# MicronetToNMEA.net
KiCad netlist of a schematic drawn in EasyEDA Pro
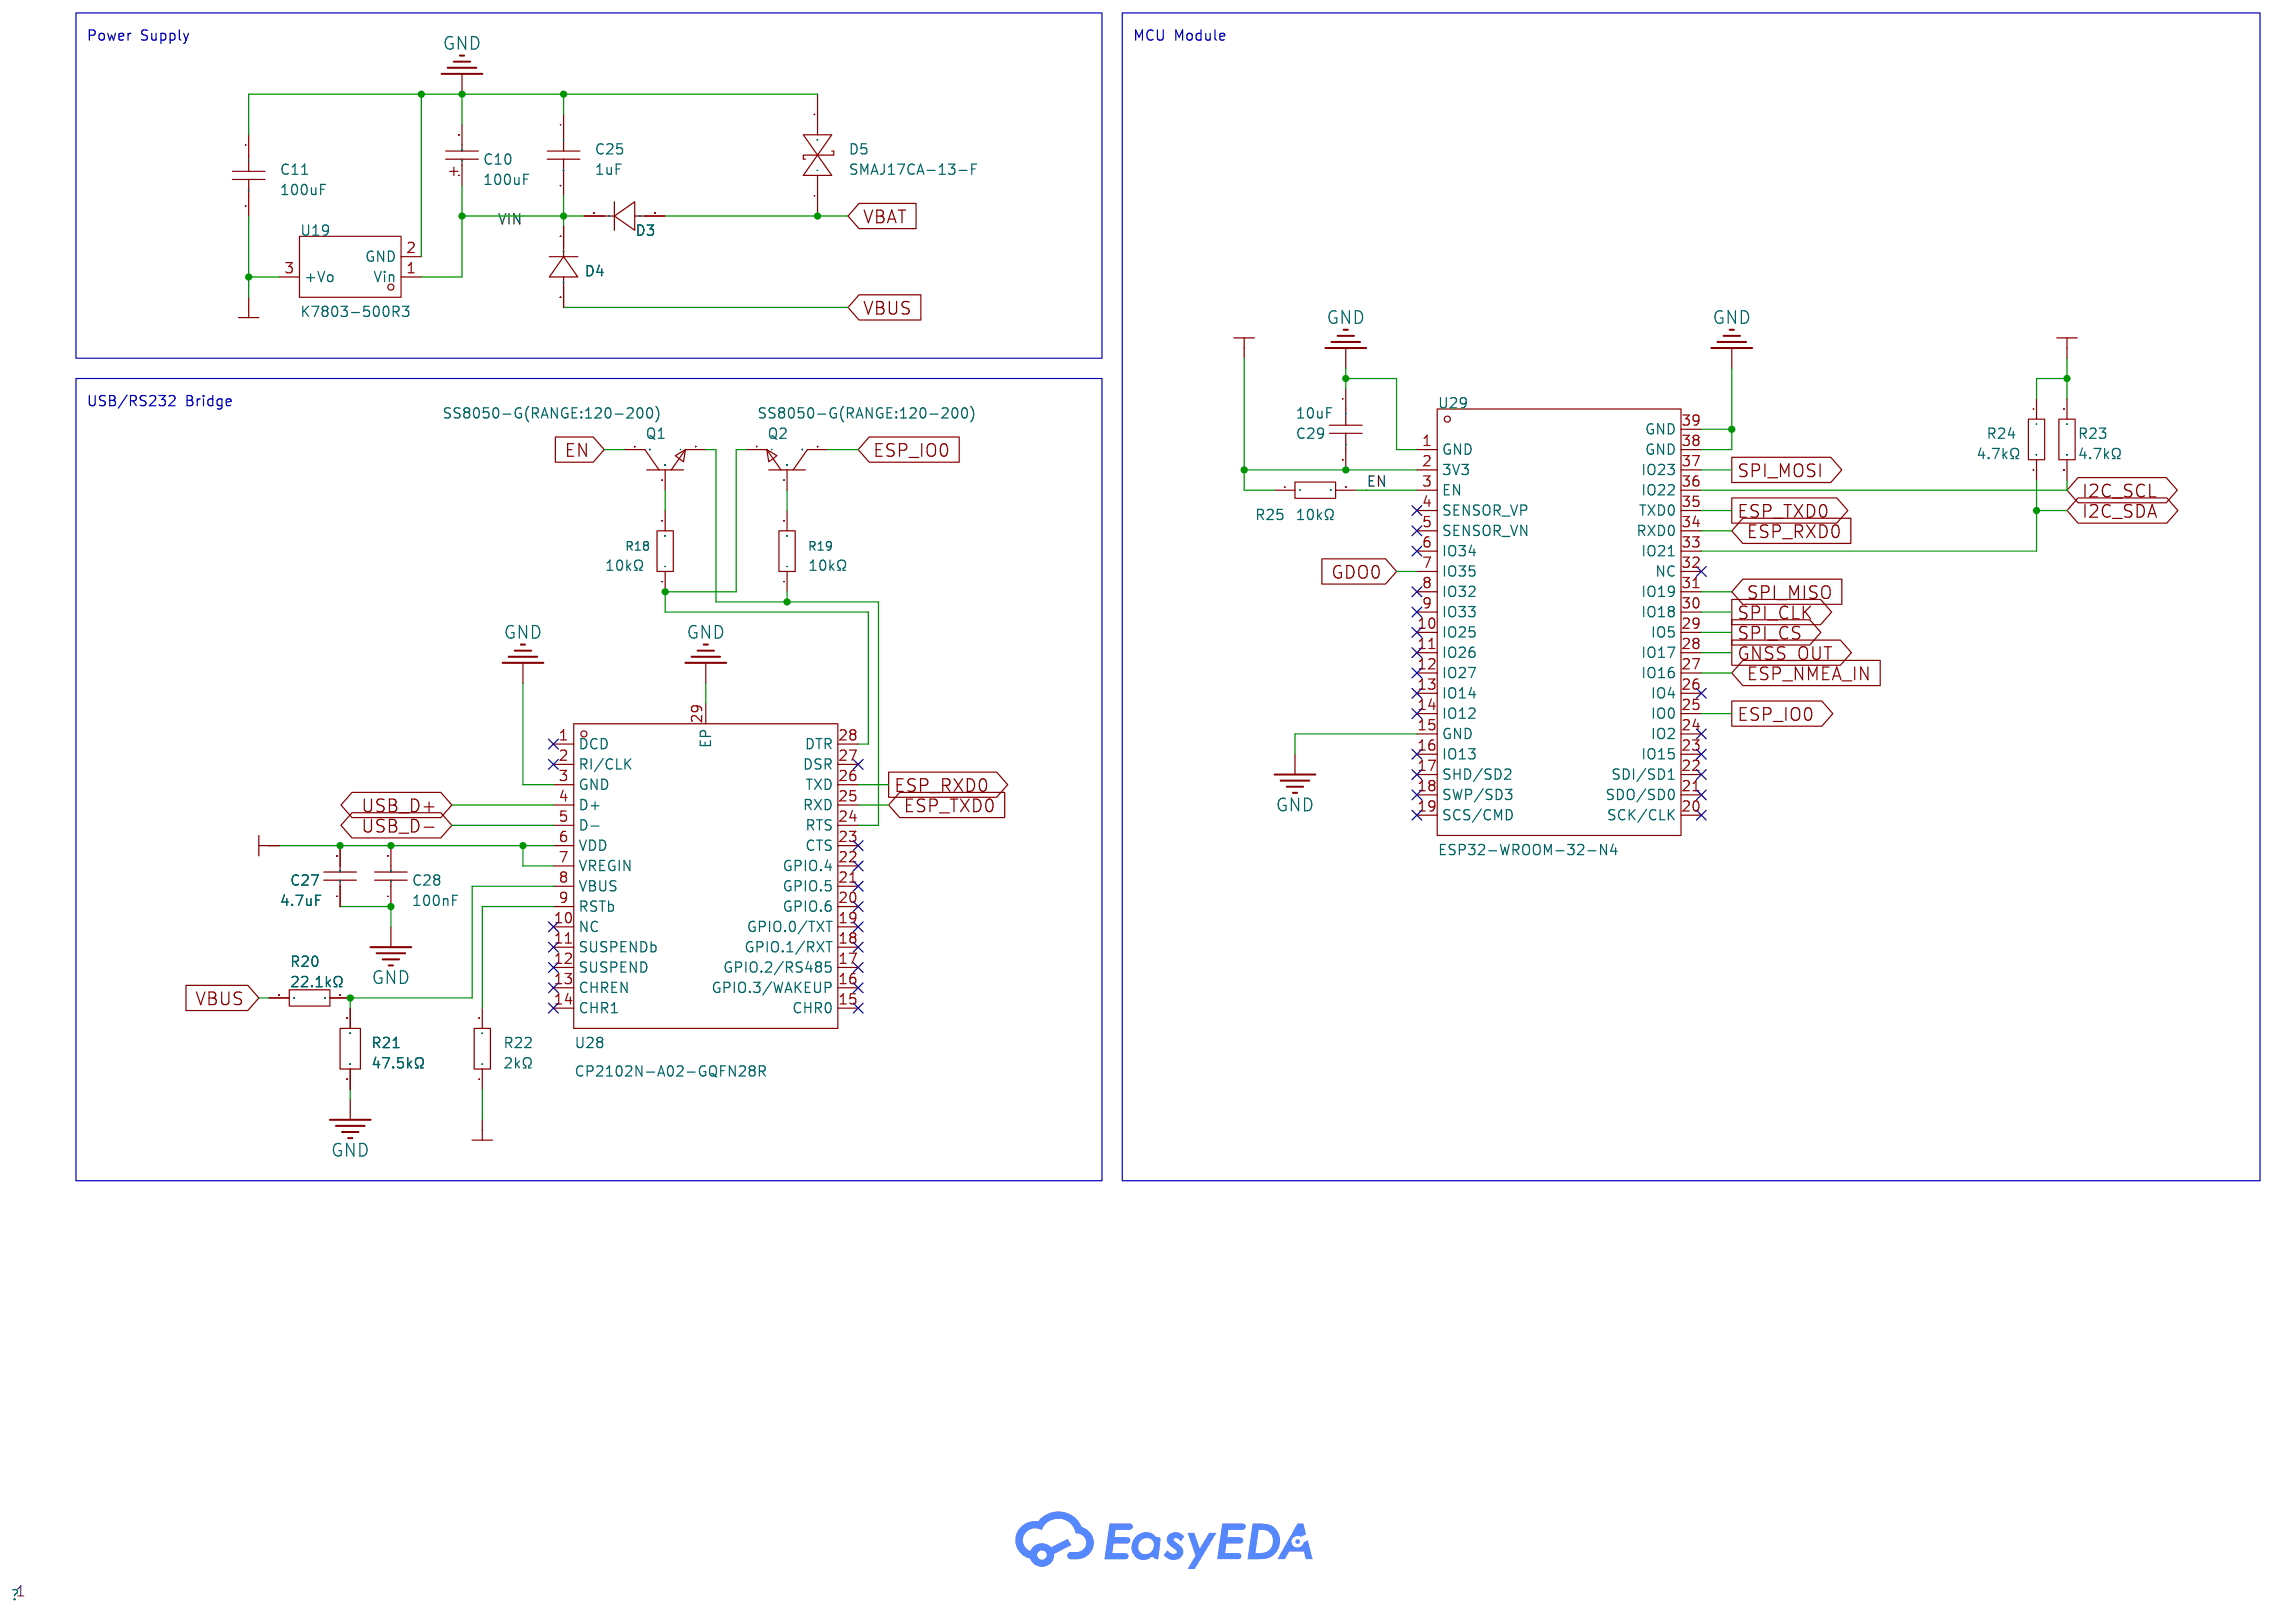
[diagram p0: MCU]
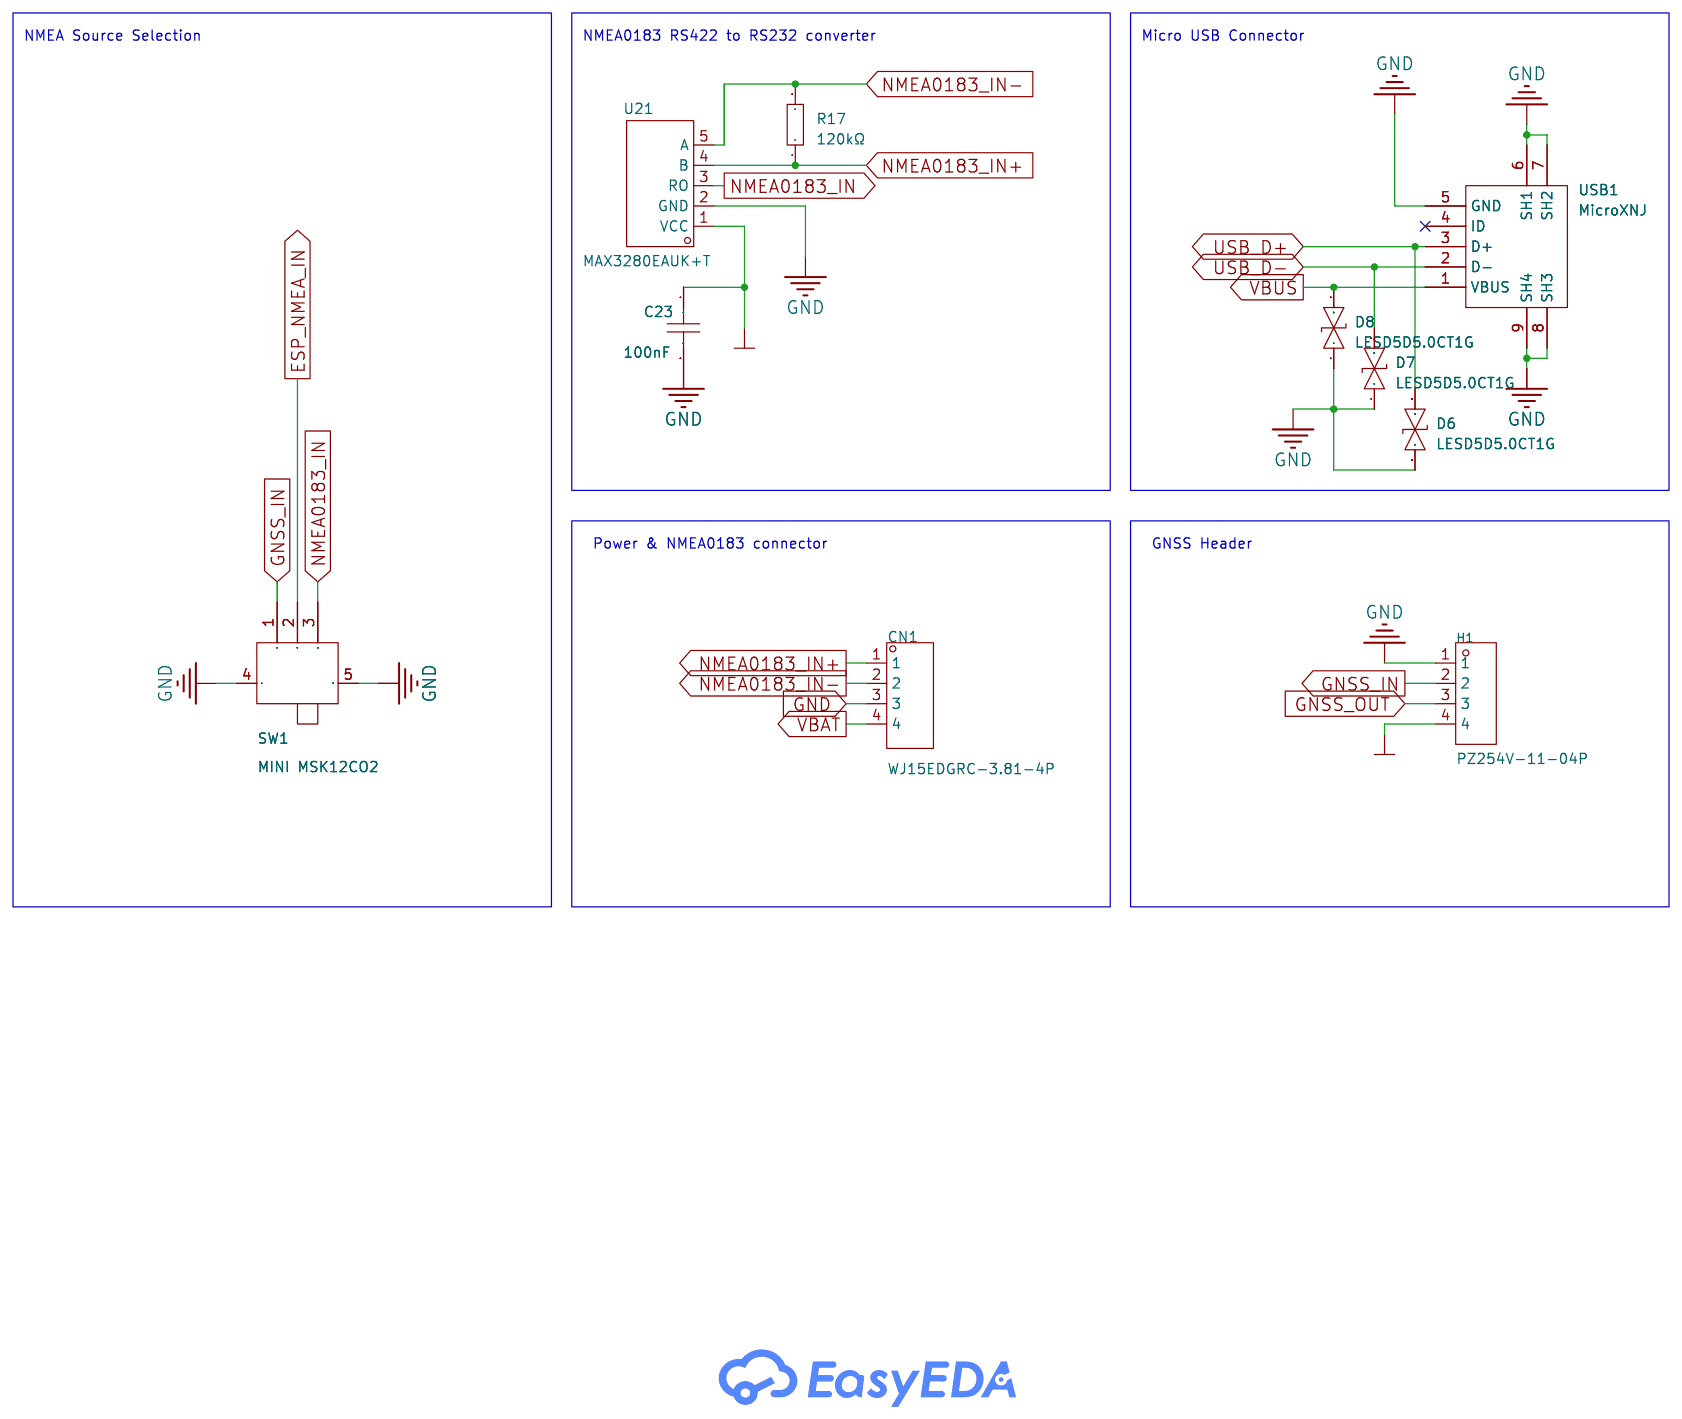
[diagram p1: Peripherals]
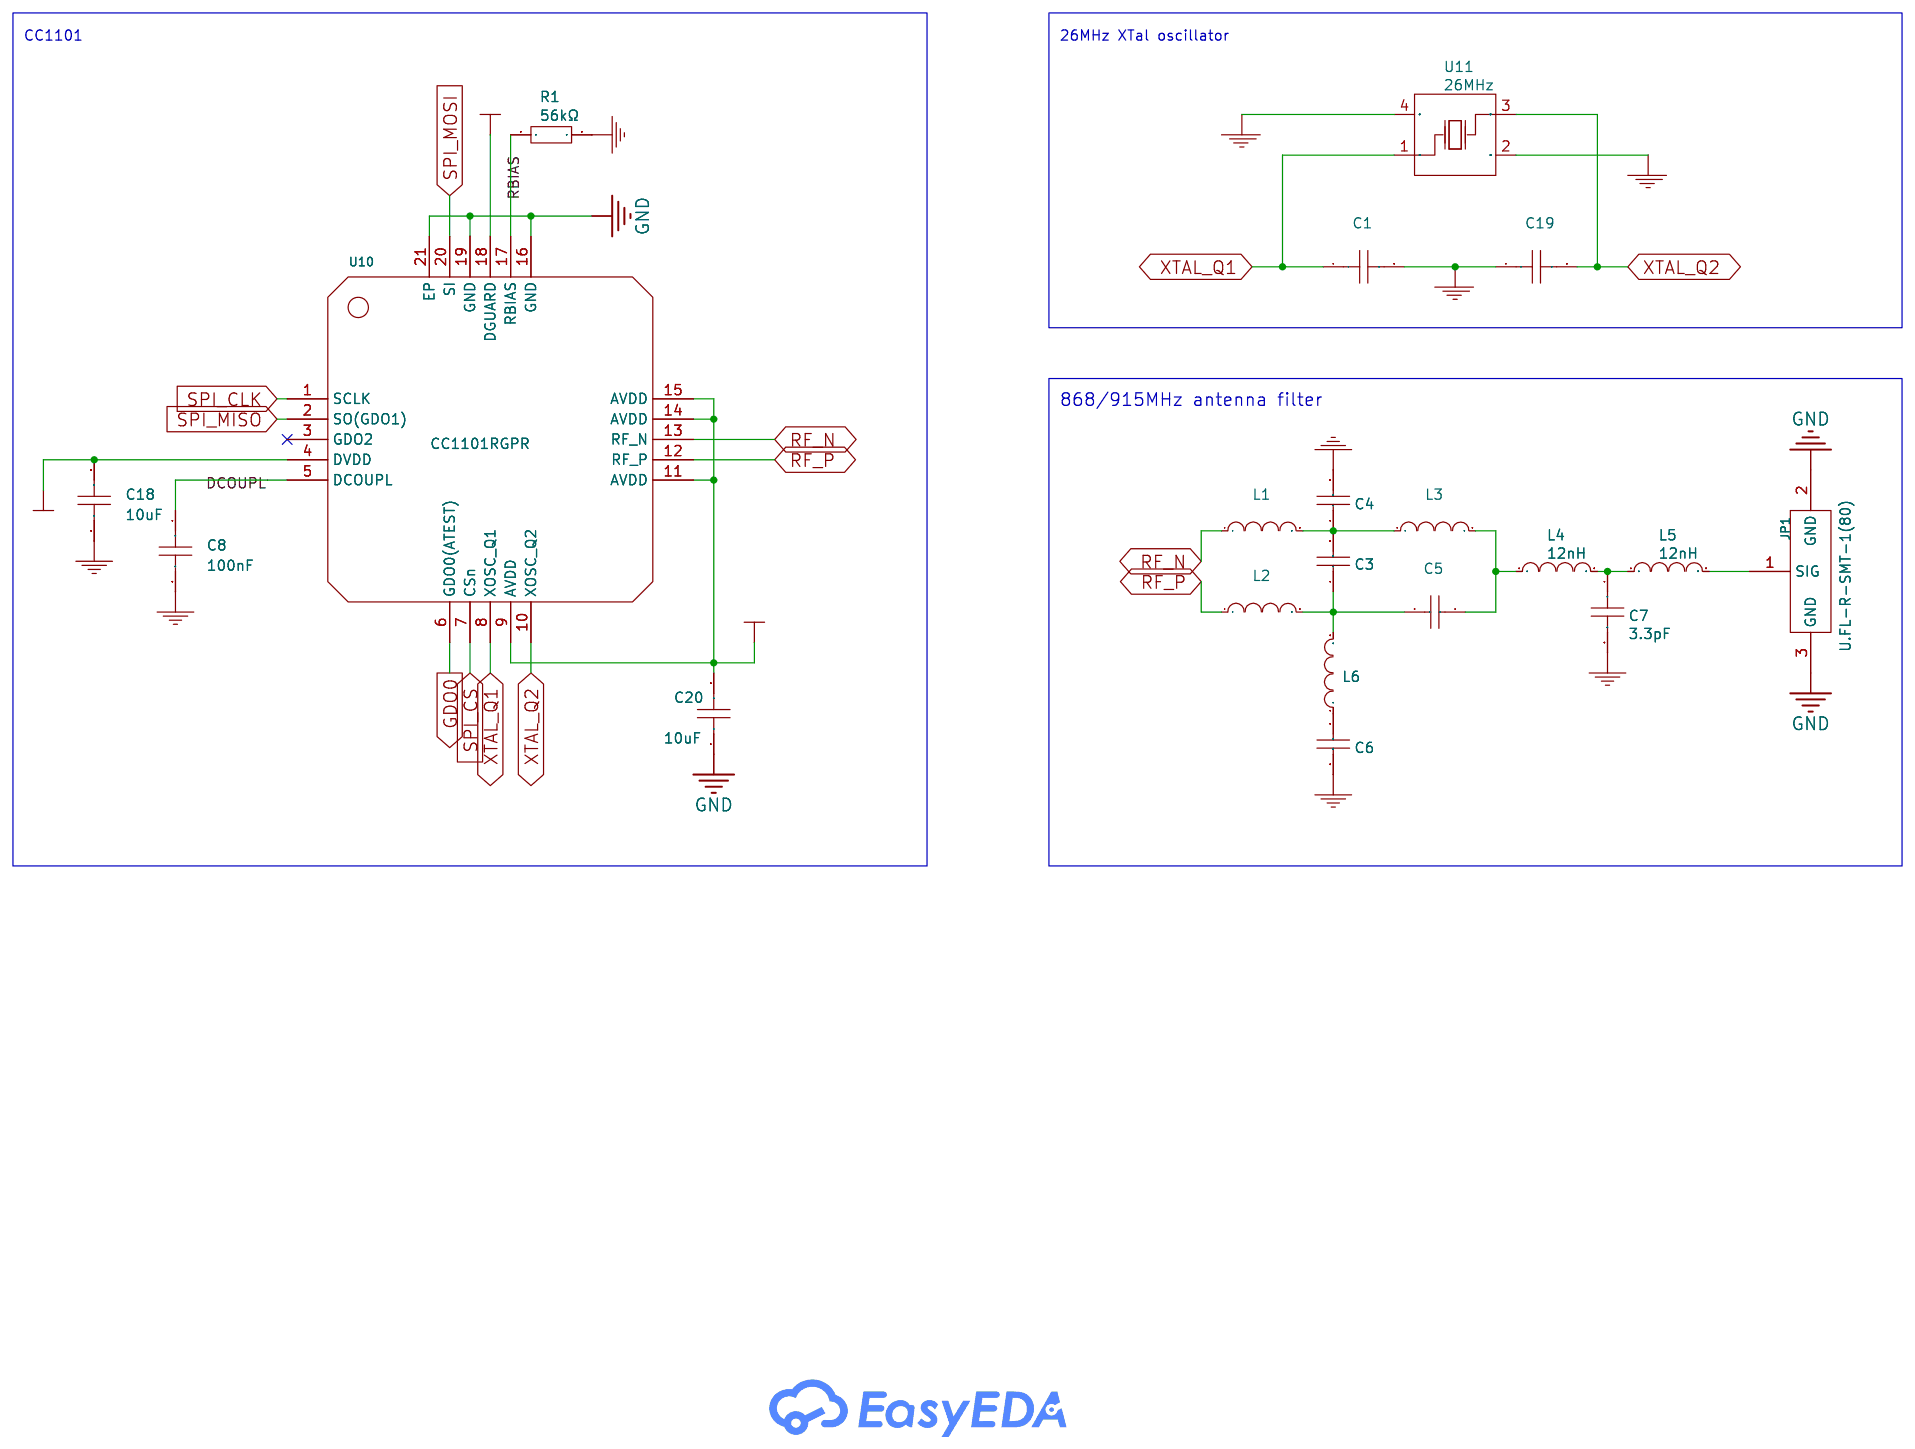
[diagram p2: Micronet RF]
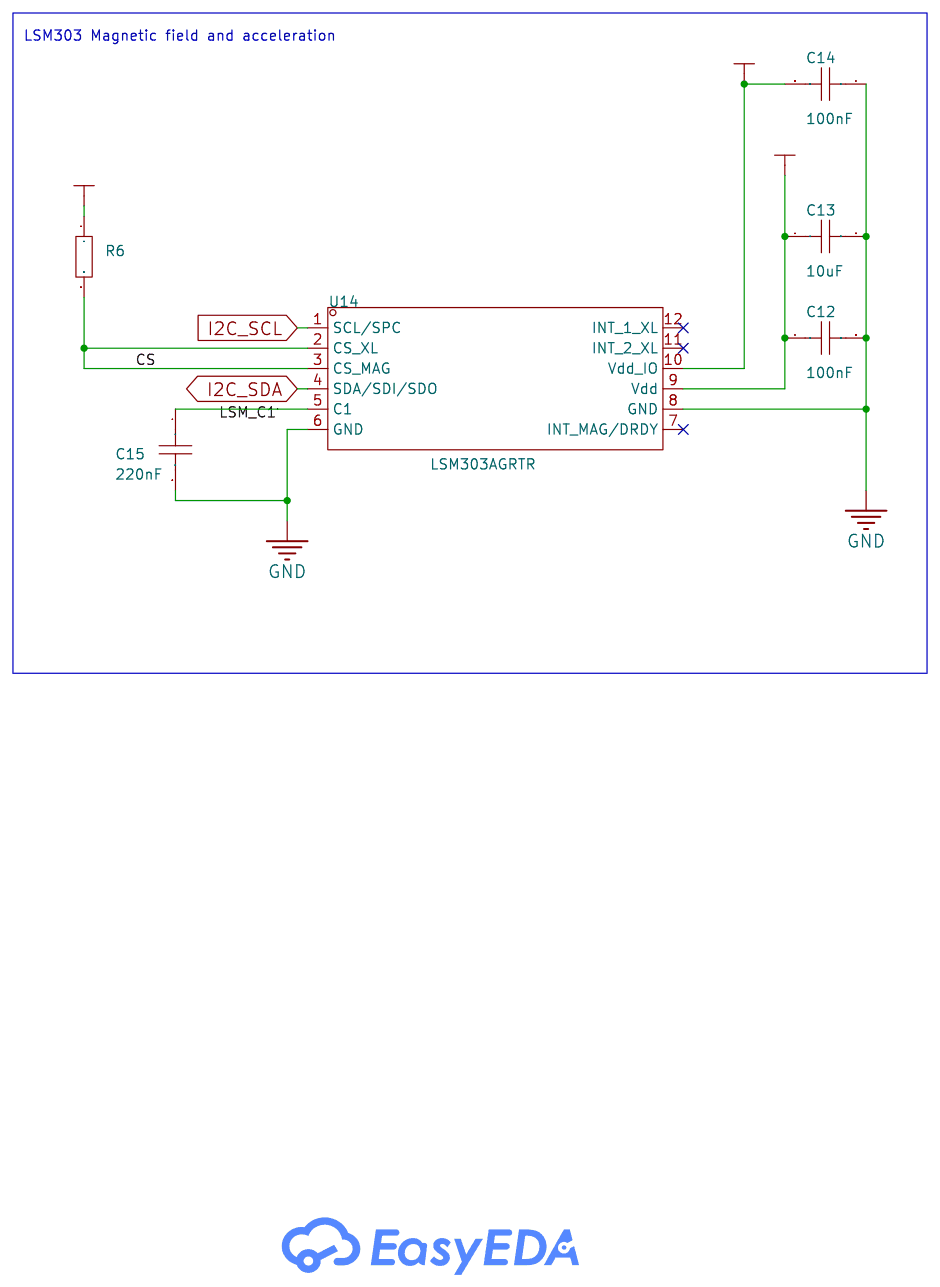
[diagram p3: Sensors]

(export (version "E")
  (design (tool "Eeschema 10.0.6"))
  (components
    (comp (ref "C10")
      (value "100uF")
      (fields (field (name "Manufacturer Part") "EEEFK1H101P") (field (name "Manufacturer") "PANASONIC(松下)"))
      (libsource (lib "easyedapro") (part "C_Ele_SMD"))
    )
    (comp (ref "C11")
      (value "100uF")
      (footprint "easyedapro:C0603")
      (fields
        (field (name "Manufacturer Part") "EMK325ABJ107MM-P")
        (field (name "Manufacturer") "TAIYO YUDEN(太诱)")
      )
      (libsource (lib "easyedapro") (part "CAP"))
    )
    (comp (ref "C25")
      (value "1uF")
      (footprint "easyedapro:C0603")
      (fields
        (field (name "Manufacturer Part") "GRM155R61H105KE05D")
        (field (name "Manufacturer") "muRata(村田)")
      )
      (libsource (lib "easyedapro") (part "CAP"))
    )
    (comp (ref "C27")
      (value "4.7uF")
      (footprint "easyedapro:C0603")
      (description "Capacitance:4.7uF Tolerance:±10% Tolerance:±10% Voltage Rating:6.3V Temperature Coefficient:X5R")
      (fields
        (field (name "Manufacturer Part") "CL10A475KQ8NNNC")
        (field (name "Manufacturer") "SAMSUNG(三星)")
      )
      (libsource (lib "easyedapro") (part "CL10A475KQ8NNNC"))
    )
    (comp (ref "C28")
      (value "100nF")
      (footprint "easyedapro:C0603")
      (description "Capacitance:100nF Tolerance:±10% Tolerance:±10% Voltage Rating:50V Temperature Coefficient:X7R")
      (fields (field (name "Manufacturer Part") "0603B104K500NT") (field (name "Manufacturer") "FH(风华)"))
      (libsource (lib "easyedapro") (part "0603B104K500NT"))
    )
    (comp (ref "C29")
      (value "10uF")
      (footprint "easyedapro:C0603")
      (fields
        (field (name "Manufacturer Part") "CL10A106MO8NQNC")
        (field (name "Manufacturer") "SAMSUNG(三星)")
      )
      (libsource (lib "easyedapro") (part "CAP"))
    )
    (comp (ref "D3")
      (value "1N4007WS")
      (fields (field (name "Manufacturer") "MDD(辰达半导体)"))
      (libsource (lib "easyedapro") (part "D_1N4007"))
    )
    (comp (ref "D4")
      (value "1N4007WS")
      (fields (field (name "Manufacturer") "MDD(辰达半导体)"))
      (libsource (lib "easyedapro") (part "D_1N4007"))
    )
    (comp (ref "D5")
      (value "SMAJ17CA-13-F")
      (footprint "easyedapro:SMA_L4.4-W2.6-LS5.0-BI")
      (fields (field (name "Manufacturer") "DIODES(美台)"))
      (libsource (lib "easyedapro") (part "SMAJ17CA-13-F"))
    )
    (comp (ref "Q1")
      (value "SS8050-G(RANGE:120-200)")
      (footprint "easyedapro:SOT-23-3_L2.9-W1.3-P1.90-LS2.4-BR")
      (fields (field (name "Manufacturer") "CJ(江苏长电/长晶)"))
      (libsource (lib "easyedapro") (part "SS8050-G"))
    )
    (comp (ref "Q2")
      (value "SS8050-G(RANGE:120-200)")
      (footprint "easyedapro:SOT-23-3_L2.9-W1.3-P1.90-LS2.4-BR")
      (fields (field (name "Manufacturer") "CJ(江苏长电/长晶)"))
      (libsource (lib "easyedapro") (part "SS8050-G"))
    )
    (comp (ref "R18")
      (value "10kΩ")
      (footprint "easyedapro:R0603")
      (fields (field (name "Manufacturer Part") "RMC060310K5%N") (field (name "Manufacturer") "Tyohm(幸亚电阻)"))
      (libsource (lib "easyedapro") (part "RMC060310K5%N"))
    )
    (comp (ref "R19")
      (value "10kΩ")
      (footprint "easyedapro:R0603")
      (fields (field (name "Manufacturer Part") "RMC060310K5%N") (field (name "Manufacturer") "Tyohm(幸亚电阻)"))
      (libsource (lib "easyedapro") (part "RMC060310K5%N"))
    )
    (comp (ref "R20")
      (value "22.1kΩ")
      (footprint "easyedapro:R0603")
      (fields (field (name "Manufacturer Part") "RC0603FR-0722K1L") (field (name "Manufacturer") "YAGEO(国巨)"))
      (libsource (lib "easyedapro") (part "RC0603FR-0722K1L"))
    )
    (comp (ref "R21")
      (value "47.5kΩ")
      (footprint "easyedapro:R0603")
      (fields (field (name "Manufacturer Part") "RT0603FRE0747K5L") (field (name "Manufacturer") "YAGEO(国巨)"))
      (libsource (lib "easyedapro") (part "RT0603FRE0747K5L"))
    )
    (comp (ref "R22")
      (value "2kΩ")
      (footprint "easyedapro:R0603")
      (fields (field (name "Manufacturer Part") "RTT03202JTP") (field (name "Manufacturer") "RALEC(旺诠)"))
      (libsource (lib "easyedapro") (part "RTT03202JTP"))
    )
    (comp (ref "R23")
      (value "4.7kΩ")
      (footprint "easyedapro:R0603")
      (fields
        (field (name "Manufacturer Part") "0402WGJ0472TCE")
        (field (name "Manufacturer") "UNI-ROYAL(厚声)")
      )
      (libsource (lib "easyedapro") (part "Res"))
    )
    (comp (ref "R24")
      (value "4.7kΩ")
      (footprint "easyedapro:R0603")
      (fields
        (field (name "Manufacturer Part") "0402WGJ0472TCE")
        (field (name "Manufacturer") "UNI-ROYAL(厚声)")
      )
      (libsource (lib "easyedapro") (part "Res"))
    )
    (comp (ref "R25")
      (value "10kΩ")
      (footprint "easyedapro:R0603")
      (fields
        (field (name "Manufacturer Part") "0402WGJ0103TCE")
        (field (name "Manufacturer") "UNI-ROYAL(厚声)")
      )
      (libsource (lib "easyedapro") (part "Res"))
    )
    (comp (ref "U19")
      (value "K7803-500R3")
      (footprint "easyedapro:PWRM-TH_K7803-500R3")
      (fields (field (name "Manufacturer") "YLPTEC(易川)"))
      (libsource (lib "easyedapro") (part "K7803-500R3_C5369643"))
    )
    (comp (ref "U28")
      (value "CP2102N-A02-GQFN28R")
      (footprint "easyedapro:QFN-28_L5.0-W5.0-P0.50-TL-EP3.3")
      (fields (field (name "Manufacturer") "SKYWORKS/SILICON LABS(芯科)"))
      (libsource (lib "easyedapro") (part "CP2102N-A02-GQFN28R"))
    )
    (comp (ref "U29")
      (value "ESP32-WROOM-32-N4")
      (footprint "easyedapro:WIFIM-SMD_ESP32-WROOM-32-N4")
      (fields (field (name "Manufacturer") "ESPRESSIF(乐鑫)"))
      (libsource (lib "easyedapro") (part "ESP32-WROOM-32"))
    )
    (comp (ref "C23")
      (value "100nF")
      (footprint "easyedapro:C0603")
      (fields
        (field (name "Manufacturer Part") "CL05B104KO5NNNC")
        (field (name "Manufacturer") "SAMSUNG(三星)")
      )
      (libsource (lib "easyedapro") (part "CAP"))
    )
    (comp (ref "CN1")
      (value "WJ15EDGRC-3.81-4P")
      (footprint "easyedapro:CONN-TH_WJ15EDGRC-3.81-4P")
      (fields (field (name "Manufacturer") "KANGNEX(康奈克斯电气)"))
      (libsource (lib "easyedapro") (part "WJ15EDGRC-3.81-4P"))
    )
    (comp (ref "D6")
      (value "LESD5D5.0CT1G")
      (footprint "easyedapro:SOD-523_L1.2-W0.8-LS1.6-BI")
      (fields (field (name "Manufacturer") "GOODWORK(固得沃克)"))
      (libsource (lib "easyedapro") (part "LESD5D5.0CT1G_C41399463"))
    )
    (comp (ref "D7")
      (value "LESD5D5.0CT1G")
      (footprint "easyedapro:SOD-523_L1.2-W0.8-LS1.6-BI")
      (fields (field (name "Manufacturer") "GOODWORK(固得沃克)"))
      (libsource (lib "easyedapro") (part "LESD5D5.0CT1G_C41399463"))
    )
    (comp (ref "D8")
      (value "LESD5D5.0CT1G")
      (footprint "easyedapro:SOD-523_L1.2-W0.8-LS1.6-BI")
      (fields (field (name "Manufacturer") "GOODWORK(固得沃克)"))
      (libsource (lib "easyedapro") (part "LESD5D5.0CT1G_C41399463"))
    )
    (comp (ref "H1")
      (value "PZ254V-11-04P")
      (footprint "easyedapro:HDR-TH_4P-P2.54-V-M")
      (fields (field (name "Manufacturer") "XFCN(兴飞)"))
      (libsource (lib "easyedapro") (part "PZ254V-11-04P_C2691448"))
    )
    (comp (ref "R17")
      (value "120kΩ")
      (footprint "easyedapro:R0603")
      (fields
        (field (name "Manufacturer Part") "0603WAF1203T5E")
        (field (name "Manufacturer") "UNI-ROYAL(厚声)")
      )
      (libsource (lib "easyedapro") (part "Res"))
    )
    (comp (ref "SW1")
      (value "MINI MSK12CO2")
      (footprint "easyedapro:SW-SMD_MSK12CO2")
      (fields (field (name "Manufacturer") "SHOU HAN(首韩)"))
      (libsource (lib "easyedapro") (part "MINI MSK12CO2"))
    )
    (comp (ref "U21")
      (value "MAX3280EAUK+T")
      (footprint "easyedapro:SOT-23-5_L3.0-W1.7-P0.95-LS2.8-BL")
      (fields (field (name "Manufacturer") "ADI(亚德诺)/MAXIM(美信)"))
      (libsource (lib "easyedapro") (part "MAX3280EAUK+T"))
    )
    (comp (ref "USB1")
      (value "MicroXNJ")
      (footprint "easyedapro:MICRO-USB-SMD_MICROXNJ")
      (fields (field (name "Manufacturer") "SHOU HAN(首韩)"))
      (libsource (lib "easyedapro") (part "MICROXNJ"))
    )
    (comp (ref "C1")
      (value "27pF")
      (footprint "easyedapro:C0402")
      (fields
        (field (name "Manufacturer Part") "GJM1555C1H270FB01D")
        (field (name "Manufacturer") "muRata(村田)")
      )
      (libsource (lib "easyedapro") (part "GJM1555C1H270FB01D"))
    )
    (comp (ref "C3")
      (value "1pF")
      (footprint "easyedapro:C0402")
      (fields
        (field (name "Manufacturer Part") "GRM1555C1H1R0CA01D")
        (field (name "Manufacturer") "muRata(村田)")
      )
      (libsource (lib "easyedapro") (part "GRM1555C1H1R0CA01D"))
    )
    (comp (ref "C4")
      (value "1.5pF")
      (footprint "easyedapro:C0402")
      (fields
        (field (name "Manufacturer Part") "GRM1555C1H1R5BA01D")
        (field (name "Manufacturer") "muRata(村田)")
      )
      (libsource (lib "easyedapro") (part "GRM1555C1H1R5BA01D"))
    )
    (comp (ref "C5")
      (value "1.5pF")
      (footprint "easyedapro:C0402")
      (fields
        (field (name "Manufacturer Part") "GRM1555C1H1R5BA01D")
        (field (name "Manufacturer") "muRata(村田)")
      )
      (libsource (lib "easyedapro") (part "GRM1555C1H1R5BA01D"))
    )
    (comp (ref "C6")
      (value "100pF")
      (footprint "easyedapro:C0402")
      (fields
        (field (name "Manufacturer Part") "GRM1555C1H101JA01D")
        (field (name "Manufacturer") "muRata(村田)")
      )
      (libsource (lib "easyedapro") (part "GRM1555C1H101JA01D"))
    )
    (comp (ref "C7")
      (value "3.3pF")
      (fields (field (name "Manufacturer") "muRata(村田)"))
      (libsource (lib "easyedapro") (part "3.3pF"))
    )
    (comp (ref "C8")
      (value "100nF")
      (footprint "easyedapro:C0402")
      (fields
        (field (name "Manufacturer Part") "GRM155R62A104KE14D")
        (field (name "Manufacturer") "muRata(村田)")
      )
      (libsource (lib "easyedapro") (part "GRM155R62A104KE14D"))
    )
    (comp (ref "C18")
      (value "10uF")
      (footprint "easyedapro:C0603")
      (fields
        (field (name "Manufacturer Part") "GRM155R61A106ME44D")
        (field (name "Manufacturer") "muRata(村田)")
      )
      (libsource (lib "easyedapro") (part "CAP"))
    )
    (comp (ref "C19")
      (value "27pF")
      (footprint "easyedapro:C0402")
      (fields
        (field (name "Manufacturer Part") "GJM1555C1H270FB01D")
        (field (name "Manufacturer") "muRata(村田)")
      )
      (libsource (lib "easyedapro") (part "GJM1555C1H270FB01D"))
    )
    (comp (ref "C20")
      (value "10uF")
      (footprint "easyedapro:C0603")
      (fields
        (field (name "Manufacturer Part") "GRM155R61A106ME44D")
        (field (name "Manufacturer") "muRata(村田)")
      )
      (libsource (lib "easyedapro") (part "CAP"))
    )
    (comp (ref "JP1")
      (value "U.FL-R-SMT-1(80)")
      (footprint "easyedapro:RF-SMD_FRF05002-JSS103M")
      (fields (field (name "Manufacturer") "HRS(广濑)"))
      (libsource (lib "easyedapro") (part "U.FL-R-SMT-1(80)"))
    )
    (comp (ref "L1")
      (value "12nH")
      (footprint "easyedapro:L0402")
      (fields (field (name "Manufacturer Part") "LQW15AN12NJ00D") (field (name "Manufacturer") "muRata(村田)"))
      (libsource (lib "easyedapro") (part "LQW15AN12NJ00D"))
    )
    (comp (ref "L2")
      (value "12nH")
      (footprint "easyedapro:L0402")
      (fields (field (name "Manufacturer Part") "LQW15AN12NJ00D") (field (name "Manufacturer") "muRata(村田)"))
      (libsource (lib "easyedapro") (part "LQW15AN12NJ00D"))
    )
    (comp (ref "L3") (value "18nH") (libsource (lib "easyedapro") (part "LQW15AN18NG00D")))
    (comp (ref "L4")
      (value "12nH")
      (footprint "easyedapro:L0402")
      (fields (field (name "Manufacturer Part") "LQW15AN12NG00D") (field (name "Manufacturer") "muRata(村田)"))
      (libsource (lib "easyedapro") (part "LQW15AN12NG00D"))
    )
    (comp (ref "L5")
      (value "12nH")
      (footprint "easyedapro:L0402")
      (fields (field (name "Manufacturer Part") "LQW15AN12NG00D") (field (name "Manufacturer") "muRata(村田)"))
      (libsource (lib "easyedapro") (part "LQW15AN12NG00D"))
    )
    (comp (ref "L6") (value "18nH") (libsource (lib "easyedapro") (part "LQW15AN18NG00D")))
    (comp (ref "R1")
      (value "56kΩ")
      (footprint "easyedapro:R0402")
      (fields (field (name "Manufacturer Part") "RK73H1ETTP5602F") (field (name "Manufacturer") "KOA"))
      (libsource (lib "easyedapro") (part "RK73H1ETTP5602F"))
    )
    (comp (ref "U10")
      (value "CC1101RGPR")
      (footprint "easyedapro:QFN-20_L4.0-W4.0-P0.5-TL-EP")
      (fields (field (name "Manufacturer") "TI(德州仪器)"))
      (libsource (lib "easyedapro") (part "CC1101RGPR"))
    )
    (comp (ref "U11") (value "26MHz") (libsource (lib "easyedapro") (part "26MHz")))
    (comp (ref "C12")
      (value "100nF")
      (footprint "easyedapro:C0603")
      (fields
        (field (name "Manufacturer Part") "CL05B104KO5NNNC")
        (field (name "Manufacturer") "SAMSUNG(三星)")
      )
      (libsource (lib "easyedapro") (part "CAP"))
    )
    (comp (ref "C13")
      (value "10uF")
      (footprint "easyedapro:C0603")
      (fields
        (field (name "Manufacturer Part") "GRM155R60J106ME44D")
        (field (name "Manufacturer") "muRata(村田)")
      )
      (libsource (lib "easyedapro") (part "CAP"))
    )
    (comp (ref "C14")
      (value "100nF")
      (footprint "easyedapro:C0603")
      (fields
        (field (name "Manufacturer Part") "CL05B104KO5NNNC")
        (field (name "Manufacturer") "SAMSUNG(三星)")
      )
      (libsource (lib "easyedapro") (part "CAP"))
    )
    (comp (ref "C15")
      (value "220nF")
      (footprint "easyedapro:C0603")
      (fields
        (field (name "Manufacturer Part") "CL05B224KO5NNNC")
        (field (name "Manufacturer") "SAMSUNG(三星)")
      )
      (libsource (lib "easyedapro") (part "CAP"))
    )
    (comp (ref "R6")
      (value "10kΩ")
      (footprint "easyedapro:R0603")
      (fields (field (name "Manufacturer") "UNI-ROYAL(厚声)"))
      (libsource (lib "easyedapro") (part "Res"))
    )
    (comp (ref "U14")
      (value "LSM303AGRTR")
      (footprint "easyedapro:LGA-12_L2.0-W2.0-P0.50-BL")
      (description "Sensor Type:加速度传感器 Operating Temperature:-40°C~+85°C Operating Temperature:-40°C~+85°C")
      (fields (field (name "Manufacturer") "ST(意法半导体)"))
      (libsource (lib "easyedapro") (part "LSM303AGRTR"))
    )
  )
  (nets
    (net (code "1") (name "+3.3V") (class "Default")
      (node (ref "C11") (pin "2") (pinfunction "2_2") (pintype "input"))
      (node (ref "C12") (pin "1") (pinfunction "1_1") (pintype "input"))
      (node (ref "C13") (pin "1") (pinfunction "1_1") (pintype "input"))
      (node (ref "C14") (pin "2") (pinfunction "2_2") (pintype "input"))
      (node (ref "C18") (pin "2") (pinfunction "2_2") (pintype "input"))
      (node (ref "C20") (pin "2") (pinfunction "2_2") (pintype "input"))
      (node (ref "C23") (pin "1") (pinfunction "1_1") (pintype "input"))
      (node (ref "C27") (pin "2") (pinfunction "2_2") (pintype "input"))
      (node (ref "C28") (pin "2") (pinfunction "2_2") (pintype "input"))
      (node (ref "C29") (pin "2") (pinfunction "2_2") (pintype "input"))
      (node (ref "H1") (pin "4") (pinfunction "4_4") (pintype "input"))
      (node (ref "R22") (pin "1") (pinfunction "1_1") (pintype "input"))
      (node (ref "R23") (pin "1") (pinfunction "1_1") (pintype "input"))
      (node (ref "R24") (pin "1") (pinfunction "1_1") (pintype "input"))
      (node (ref "R25") (pin "1") (pinfunction "1_1") (pintype "input"))
      (node (ref "R6") (pin "1") (pinfunction "1_1") (pintype "input"))
      (node (ref "U10") (pin "11") (pinfunction "AVDD_11") (pintype "input"))
      (node (ref "U10") (pin "14") (pinfunction "AVDD_14") (pintype "input"))
      (node (ref "U10") (pin "15") (pinfunction "AVDD_15") (pintype "input"))
      (node (ref "U10") (pin "18") (pinfunction "DGUARD_18") (pintype "input"))
      (node (ref "U10") (pin "4") (pinfunction "DVDD_4") (pintype "input"))
      (node (ref "U10") (pin "9") (pinfunction "AVDD_9") (pintype "input"))
      (node (ref "U14") (pin "10") (pinfunction "Vdd_IO_10") (pintype "unspecified"))
      (node (ref "U14") (pin "9") (pinfunction "Vdd_9") (pintype "unspecified"))
      (node (ref "U19") (pin "3") (pinfunction "+Vo_3") (pintype "unspecified"))
      (node (ref "U21") (pin "1") (pinfunction "VCC_1") (pintype "unspecified"))
      (node (ref "U28") (pin "6") (pinfunction "VDD_6") (pintype "unspecified"))
      (node (ref "U28") (pin "7") (pinfunction "VREGIN_7") (pintype "unspecified"))
      (node (ref "U29") (pin "2") (pinfunction "3V3_2") (pintype "unspecified"))
    )
    (net (code "2") (name "CS") (class "Default")
      (node (ref "R6") (pin "2") (pinfunction "2_2") (pintype "input"))
      (node (ref "U14") (pin "2") (pinfunction "CS_XL_2") (pintype "unspecified"))
      (node (ref "U14") (pin "3") (pinfunction "CS_MAG_3") (pintype "unspecified"))
    )
    (net (code "3") (name "DCOUPL") (class "Default")
      (node (ref "C8") (pin "1") (pinfunction "1_1") (pintype "input"))
      (node (ref "U10") (pin "5") (pinfunction "DCOUPL_5") (pintype "input"))
    )
    (net (code "4") (name "EN") (class "Default")
      (node (ref "Q1") (pin "3") (pinfunction "C_3") (pintype "input"))
      (node (ref "R25") (pin "2") (pinfunction "2_2") (pintype "input"))
      (node (ref "U29") (pin "3") (pinfunction "EN_3") (pintype "unspecified"))
    )
    (net (code "5") (name "ESP_IO0") (class "Default")
      (node (ref "Q2") (pin "3") (pinfunction "C_3") (pintype "input"))
      (node (ref "U29") (pin "25") (pinfunction "IO0_25") (pintype "unspecified"))
    )
    (net (code "6") (name "ESP_NMEA_IN") (class "Default")
      (node (ref "SW1") (pin "2") (pinfunction "2_2") (pintype "unspecified"))
      (node (ref "U29") (pin "27") (pinfunction "IO16_27") (pintype "unspecified"))
    )
    (net (code "7") (name "ESP_RXD0") (class "Default")
      (node (ref "U28") (pin "26") (pinfunction "TXD_26") (pintype "unspecified"))
      (node (ref "U29") (pin "34") (pinfunction "RXD0_34") (pintype "unspecified"))
    )
    (net (code "8") (name "ESP_TXD0") (class "Default")
      (node (ref "U28") (pin "25") (pinfunction "RXD_25") (pintype "unspecified"))
      (node (ref "U29") (pin "35") (pinfunction "TXD0_35") (pintype "unspecified"))
    )
    (net (code "9") (name "GDO0") (class "Default")
      (node (ref "U10") (pin "6") (pinfunction "GDO0(ATEST)_6") (pintype "input"))
      (node (ref "U29") (pin "7") (pinfunction "IO35_7") (pintype "unspecified"))
    )
    (net (code "10") (name "GND") (class "Default")
      (node (ref "C1") (pin "2") (pinfunction "2_2") (pintype "input"))
      (node (ref "C10") (pin "2") (pinfunction "2_2") (pintype "input"))
      (node (ref "C11") (pin "1") (pinfunction "1_1") (pintype "input"))
      (node (ref "C12") (pin "2") (pinfunction "2_2") (pintype "input"))
      (node (ref "C13") (pin "2") (pinfunction "2_2") (pintype "input"))
      (node (ref "C14") (pin "1") (pinfunction "1_1") (pintype "input"))
      (node (ref "C15") (pin "2") (pinfunction "2_2") (pintype "input"))
      (node (ref "C18") (pin "1") (pinfunction "1_1") (pintype "input"))
      (node (ref "C19") (pin "1") (pinfunction "1_1") (pintype "input"))
      (node (ref "C20") (pin "1") (pinfunction "1_1") (pintype "input"))
      (node (ref "C23") (pin "2") (pinfunction "2_2") (pintype "input"))
      (node (ref "C25") (pin "1") (pinfunction "1_1") (pintype "input"))
      (node (ref "C27") (pin "1") (pinfunction "1_1") (pintype "input"))
      (node (ref "C28") (pin "1") (pinfunction "1_1") (pintype "input"))
      (node (ref "C29") (pin "1") (pinfunction "1_1") (pintype "input"))
      (node (ref "C4") (pin "2") (pinfunction "2_2") (pintype "input"))
      (node (ref "C6") (pin "2") (pinfunction "2_2") (pintype "input"))
      (node (ref "C7") (pin "2") (pinfunction "2_2") (pintype "unspecified"))
      (node (ref "C8") (pin "2") (pinfunction "2_2") (pintype "input"))
      (node (ref "CN1") (pin "3") (pinfunction "3_3") (pintype "unspecified"))
      (node (ref "D5") (pin "2") (pinfunction "2_2") (pintype "unspecified"))
      (node (ref "D6") (pin "1") (pinfunction "1_1") (pintype "unspecified"))
      (node (ref "D7") (pin "1") (pinfunction "1_1") (pintype "unspecified"))
      (node (ref "D8") (pin "1") (pinfunction "1_1") (pintype "unspecified"))
      (node (ref "H1") (pin "1") (pinfunction "1_1") (pintype "input"))
      (node (ref "JP1") (pin "2") (pinfunction "GND_2") (pintype "input"))
      (node (ref "JP1") (pin "3") (pinfunction "GND_3") (pintype "input"))
      (node (ref "R1") (pin "2") (pinfunction "2_2") (pintype "input"))
      (node (ref "R21") (pin "1") (pinfunction "1_1") (pintype "input"))
      (node (ref "SW1") (pin "4") (pinfunction "4_4") (pintype "unspecified"))
      (node (ref "SW1") (pin "5") (pinfunction "5_5") (pintype "unspecified"))
      (node (ref "U10") (pin "16") (pinfunction "GND_16") (pintype "input"))
      (node (ref "U10") (pin "19") (pinfunction "GND_19") (pintype "input"))
      (node (ref "U10") (pin "21") (pinfunction "EP_21") (pintype "input"))
      (node (ref "U11") (pin "2") (pinfunction "GND_2") (pintype "unspecified"))
      (node (ref "U11") (pin "4") (pinfunction "GND_4") (pintype "unspecified"))
      (node (ref "U14") (pin "6") (pinfunction "GND_6") (pintype "unspecified"))
      (node (ref "U14") (pin "8") (pinfunction "GND_8") (pintype "unspecified"))
      (node (ref "U19") (pin "2") (pinfunction "GND_2") (pintype "unspecified"))
      (node (ref "U21") (pin "2") (pinfunction "GND_2") (pintype "unspecified"))
      (node (ref "U28") (pin "29") (pinfunction "EP_29") (pintype "unspecified"))
      (node (ref "U28") (pin "3") (pinfunction "GND_3") (pintype "unspecified"))
      (node (ref "U29") (pin "1") (pinfunction "GND_1") (pintype "unspecified"))
      (node (ref "U29") (pin "15") (pinfunction "GND_15") (pintype "unspecified"))
      (node (ref "U29") (pin "38") (pinfunction "GND_38") (pintype "unspecified"))
      (node (ref "U29") (pin "39") (pinfunction "GND_39") (pintype "unspecified"))
      (node (ref "USB1") (pin "5") (pinfunction "GND_5") (pintype "unspecified"))
      (node (ref "USB1") (pin "6") (pinfunction "SH1_6") (pintype "unspecified"))
      (node (ref "USB1") (pin "7") (pinfunction "SH2_7") (pintype "unspecified"))
      (node (ref "USB1") (pin "8") (pinfunction "SH3_8") (pintype "unspecified"))
      (node (ref "USB1") (pin "9") (pinfunction "SH4_9") (pintype "unspecified"))
    )
    (net (code "11") (name "GNSS_IN") (class "Default")
      (node (ref "H1") (pin "2") (pinfunction "2_2") (pintype "input"))
      (node (ref "SW1") (pin "1") (pinfunction "1_1") (pintype "unspecified"))
    )
    (net (code "12") (name "GNSS_OUT") (class "Default")
      (node (ref "H1") (pin "3") (pinfunction "3_3") (pintype "input"))
      (node (ref "U29") (pin "28") (pinfunction "IO17_28") (pintype "unspecified"))
    )
    (net (code "13") (name "I2C_SCL") (class "Default")
      (node (ref "R23") (pin "2") (pinfunction "2_2") (pintype "input"))
      (node (ref "U14") (pin "1") (pinfunction "SCL/SPC_1") (pintype "unspecified"))
      (node (ref "U29") (pin "36") (pinfunction "IO22_36") (pintype "unspecified"))
    )
    (net (code "14") (name "I2C_SDA") (class "Default")
      (node (ref "R24") (pin "2") (pinfunction "2_2") (pintype "input"))
      (node (ref "U14") (pin "4") (pinfunction "SDA/SDI/SDO_4") (pintype "unspecified"))
      (node (ref "U29") (pin "33") (pinfunction "IO21_33") (pintype "unspecified"))
    )
    (net (code "15") (name "LSM_C1") (class "Default")
      (node (ref "C15") (pin "1") (pinfunction "1_1") (pintype "input"))
      (node (ref "U14") (pin "5") (pinfunction "C1_5") (pintype "unspecified"))
    )
    (net (code "16") (name "NMEA0183_IN") (class "Default")
      (node (ref "SW1") (pin "3") (pinfunction "3_3") (pintype "unspecified"))
      (node (ref "U21") (pin "3") (pinfunction "RO_3") (pintype "unspecified"))
    )
    (net (code "17") (name "NMEA0183_IN+") (class "Default")
      (node (ref "CN1") (pin "1") (pinfunction "1_1") (pintype "unspecified"))
      (node (ref "R17") (pin "1") (pinfunction "1_1") (pintype "input"))
      (node (ref "U21") (pin "4") (pinfunction "B_4") (pintype "unspecified"))
    )
    (net (code "18") (name "NMEA0183_IN-") (class "Default")
      (node (ref "CN1") (pin "2") (pinfunction "2_2") (pintype "unspecified"))
      (node (ref "R17") (pin "2") (pinfunction "2_2") (pintype "input"))
      (node (ref "U21") (pin "5") (pinfunction "A_5") (pintype "unspecified"))
    )
    (net (code "19") (name "Net-(C3-Pad1)") (class "Default")
      (node (ref "C3") (pin "1") (pinfunction "1_1") (pintype "input"))
      (node (ref "C5") (pin "2") (pinfunction "2_2") (pintype "input"))
      (node (ref "L2") (pin "2") (pinfunction "2_2") (pintype "input"))
      (node (ref "L6") (pin "2") (pinfunction "2_2") (pintype "input"))
    )
    (net (code "20") (name "Net-(C3-Pad2)") (class "Default")
      (node (ref "C3") (pin "2") (pinfunction "2_2") (pintype "input"))
      (node (ref "C4") (pin "1") (pinfunction "1_1") (pintype "input"))
      (node (ref "L1") (pin "2") (pinfunction "2_2") (pintype "input"))
      (node (ref "L3") (pin "1") (pinfunction "1_1") (pintype "input"))
    )
    (net (code "21") (name "Net-(C5-Pad1)") (class "Default")
      (node (ref "C5") (pin "1") (pinfunction "1_1") (pintype "input"))
      (node (ref "L3") (pin "2") (pinfunction "2_2") (pintype "input"))
      (node (ref "L4") (pin "1") (pinfunction "1_1") (pintype "unspecified"))
    )
    (net (code "22") (name "Net-(C6-Pad1)") (class "Default")
      (node (ref "C6") (pin "1") (pinfunction "1_1") (pintype "input"))
      (node (ref "L6") (pin "1") (pinfunction "1_1") (pintype "input"))
    )
    (net (code "23") (name "Net-(C7-Pad1)") (class "Default")
      (node (ref "C7") (pin "1") (pinfunction "1_1") (pintype "unspecified"))
      (node (ref "L4") (pin "2") (pinfunction "2_2") (pintype "unspecified"))
      (node (ref "L5") (pin "1") (pinfunction "1_1") (pintype "unspecified"))
    )
    (net (code "24") (name "Net-(JP1-SIG)") (class "Default")
      (node (ref "JP1") (pin "1") (pinfunction "SIG_1") (pintype "input"))
      (node (ref "L5") (pin "2") (pinfunction "2_2") (pintype "unspecified"))
    )
    (net (code "25") (name "Net-(Q1-B)") (class "Default")
      (node (ref "Q1") (pin "1") (pinfunction "B_1") (pintype "input"))
      (node (ref "R18") (pin "2") (pinfunction "2_2") (pintype "input"))
    )
    (net (code "26") (name "Net-(Q1-E)") (class "Default")
      (node (ref "Q1") (pin "2") (pinfunction "E_2") (pintype "input"))
      (node (ref "R19") (pin "1") (pinfunction "1_1") (pintype "input"))
      (node (ref "U28") (pin "24") (pinfunction "RTS_24") (pintype "unspecified"))
    )
    (net (code "27") (name "Net-(Q2-B)") (class "Default")
      (node (ref "Q2") (pin "1") (pinfunction "B_1") (pintype "input"))
      (node (ref "R19") (pin "2") (pinfunction "2_2") (pintype "input"))
    )
    (net (code "28") (name "Net-(Q2-E)") (class "Default")
      (node (ref "Q2") (pin "2") (pinfunction "E_2") (pintype "input"))
      (node (ref "R18") (pin "1") (pinfunction "1_1") (pintype "input"))
      (node (ref "U28") (pin "28") (pinfunction "DTR_28") (pintype "unspecified"))
    )
    (net (code "29") (name "Net-(U28-RSTb)") (class "Default")
      (node (ref "R22") (pin "2") (pinfunction "2_2") (pintype "input"))
      (node (ref "U28") (pin "9") (pinfunction "RSTb_9") (pintype "unspecified"))
    )
    (net (code "30") (name "Net-(U28-VBUS)") (class "Default")
      (node (ref "R20") (pin "1") (pinfunction "1_1") (pintype "input"))
      (node (ref "R21") (pin "2") (pinfunction "2_2") (pintype "input"))
      (node (ref "U28") (pin "8") (pinfunction "VBUS_8") (pintype "unspecified"))
    )
    (net (code "31") (name "RBIAS") (class "Default")
      (node (ref "R1") (pin "1") (pinfunction "1_1") (pintype "input"))
      (node (ref "U10") (pin "17") (pinfunction "RBIAS_17") (pintype "input"))
    )
    (net (code "32") (name "RF_N") (class "Default")
      (node (ref "L1") (pin "1") (pinfunction "1_1") (pintype "input"))
      (node (ref "U10") (pin "13") (pinfunction "RF_N_13") (pintype "input"))
    )
    (net (code "33") (name "RF_P") (class "Default")
      (node (ref "L2") (pin "1") (pinfunction "1_1") (pintype "input"))
      (node (ref "U10") (pin "12") (pinfunction "RF_P_12") (pintype "input"))
    )
    (net (code "34") (name "SPI_CLK") (class "Default")
      (node (ref "U10") (pin "1") (pinfunction "SCLK_1") (pintype "input"))
      (node (ref "U29") (pin "30") (pinfunction "IO18_30") (pintype "unspecified"))
    )
    (net (code "35") (name "SPI_CS") (class "Default")
      (node (ref "U10") (pin "7") (pinfunction "CSn_7") (pintype "input"))
      (node (ref "U29") (pin "29") (pinfunction "IO5_29") (pintype "unspecified"))
    )
    (net (code "36") (name "SPI_MISO") (class "Default")
      (node (ref "U10") (pin "2") (pinfunction "SO(GDO1)_2") (pintype "input"))
      (node (ref "U29") (pin "31") (pinfunction "IO19_31") (pintype "unspecified"))
    )
    (net (code "37") (name "SPI_MOSI") (class "Default")
      (node (ref "U10") (pin "20") (pinfunction "SI_20") (pintype "input"))
      (node (ref "U29") (pin "37") (pinfunction "IO23_37") (pintype "unspecified"))
    )
    (net (code "38") (name "USB_D+") (class "Default")
      (node (ref "D6") (pin "2") (pinfunction "2_2") (pintype "unspecified"))
      (node (ref "U28") (pin "4") (pinfunction "D+_4") (pintype "unspecified"))
      (node (ref "USB1") (pin "3") (pinfunction "D+_3") (pintype "unspecified"))
    )
    (net (code "39") (name "USB_D-") (class "Default")
      (node (ref "D7") (pin "2") (pinfunction "2_2") (pintype "unspecified"))
      (node (ref "U28") (pin "5") (pinfunction "D-_5") (pintype "unspecified"))
      (node (ref "USB1") (pin "2") (pinfunction "D-_2") (pintype "unspecified"))
    )
    (net (code "40") (name "VBAT") (class "Default")
      (node (ref "CN1") (pin "4") (pinfunction "4_4") (pintype "unspecified"))
      (node (ref "D3") (pin "2") (pinfunction "A_2") (pintype "input"))
      (node (ref "D5") (pin "1") (pinfunction "1_1") (pintype "unspecified"))
    )
    (net (code "41") (name "VBUS") (class "Default")
      (node (ref "D4") (pin "2") (pinfunction "A_2") (pintype "input"))
      (node (ref "D8") (pin "2") (pinfunction "2_2") (pintype "unspecified"))
      (node (ref "R20") (pin "2") (pinfunction "2_2") (pintype "input"))
      (node (ref "USB1") (pin "1") (pinfunction "VBUS_1") (pintype "unspecified"))
    )
    (net (code "42") (name "VIN") (class "Default")
      (node (ref "C10") (pin "1") (pinfunction "1_1") (pintype "input"))
      (node (ref "C25") (pin "2") (pinfunction "2_2") (pintype "input"))
      (node (ref "D3") (pin "1") (pinfunction "K_1") (pintype "input"))
      (node (ref "D4") (pin "1") (pinfunction "K_1") (pintype "input"))
      (node (ref "U19") (pin "1") (pinfunction "Vin_1") (pintype "unspecified"))
    )
    (net (code "43") (name "XTAL_Q1") (class "Default")
      (node (ref "C1") (pin "1") (pinfunction "1_1") (pintype "input"))
      (node (ref "U10") (pin "8") (pinfunction "XOSC_Q1_8") (pintype "input"))
      (node (ref "U11") (pin "1") (pinfunction "OSC1_1") (pintype "unspecified"))
    )
    (net (code "44") (name "XTAL_Q2") (class "Default")
      (node (ref "C19") (pin "2") (pinfunction "2_2") (pintype "input"))
      (node (ref "U10") (pin "10") (pinfunction "XOSC_Q2_10") (pintype "input"))
      (node (ref "U11") (pin "3") (pinfunction "OSC2_3") (pintype "unspecified"))
    )
    (net (code "45") (name "unconnected-(U10-GDO2-Pad3)") (class "Default")
      (node (ref "U10") (pin "3") (pinfunction "GDO2_3") (pintype "input+no_connect"))
    )
    (net (code "46") (name "unconnected-(U14-INT_1_XL-Pad12)") (class "Default")
      (node (ref "U14") (pin "12") (pinfunction "INT_1_XL_12") (pintype "unspecified+no_connect"))
    )
    (net (code "47") (name "unconnected-(U14-INT_2_XL-Pad11)") (class "Default")
      (node (ref "U14") (pin "11") (pinfunction "INT_2_XL_11") (pintype "unspecified+no_connect"))
    )
    (net (code "48") (name "unconnected-(U14-INT_MAG{slash}DRDY-Pad7)") (class "Default")
      (node (ref "U14") (pin "7") (pinfunction "INT_MAG/DRDY_7") (pintype "unspecified+no_connect"))
    )
    (net (code "49") (name "unconnected-(U28-CHR0-Pad15)") (class "Default")
      (node (ref "U28") (pin "15") (pinfunction "CHR0_15") (pintype "unspecified+no_connect"))
    )
    (net (code "50") (name "unconnected-(U28-CHR1-Pad14)") (class "Default")
      (node (ref "U28") (pin "14") (pinfunction "CHR1_14") (pintype "unspecified+no_connect"))
    )
    (net (code "51") (name "unconnected-(U28-CHREN-Pad13)") (class "Default")
      (node (ref "U28") (pin "13") (pinfunction "CHREN_13") (pintype "unspecified+no_connect"))
    )
    (net (code "52") (name "unconnected-(U28-CTS-Pad23)") (class "Default")
      (node (ref "U28") (pin "23") (pinfunction "CTS_23") (pintype "unspecified+no_connect"))
    )
    (net (code "53") (name "unconnected-(U28-DCD-Pad1)") (class "Default")
      (node (ref "U28") (pin "1") (pinfunction "DCD_1") (pintype "unspecified+no_connect"))
    )
    (net (code "54") (name "unconnected-(U28-DSR-Pad27)") (class "Default")
      (node (ref "U28") (pin "27") (pinfunction "DSR_27") (pintype "unspecified+no_connect"))
    )
    (net (code "55") (name "unconnected-(U28-GPIO.0{slash}TXT-Pad19)") (class "Default")
      (node (ref "U28") (pin "19") (pinfunction "GPIO.0/TXT_19") (pintype "unspecified+no_connect"))
    )
    (net (code "56") (name "unconnected-(U28-GPIO.1{slash}RXT-Pad18)") (class "Default")
      (node (ref "U28") (pin "18") (pinfunction "GPIO.1/RXT_18") (pintype "unspecified+no_connect"))
    )
    (net (code "57") (name "unconnected-(U28-GPIO.2{slash}RS485-Pad17)") (class "Default")
      (node (ref "U28") (pin "17") (pinfunction "GPIO.2/RS485_17") (pintype "unspecified+no_connect"))
    )
    (net (code "58") (name "unconnected-(U28-GPIO.3{slash}WAKEUP-Pad16)") (class "Default")
      (node (ref "U28") (pin "16") (pinfunction "GPIO.3/WAKEUP_16") (pintype "unspecified+no_connect"))
    )
    (net (code "59") (name "unconnected-(U28-GPIO.4-Pad22)") (class "Default")
      (node (ref "U28") (pin "22") (pinfunction "GPIO.4_22") (pintype "unspecified+no_connect"))
    )
    (net (code "60") (name "unconnected-(U28-GPIO.5-Pad21)") (class "Default")
      (node (ref "U28") (pin "21") (pinfunction "GPIO.5_21") (pintype "unspecified+no_connect"))
    )
    (net (code "61") (name "unconnected-(U28-GPIO.6-Pad20)") (class "Default")
      (node (ref "U28") (pin "20") (pinfunction "GPIO.6_20") (pintype "unspecified+no_connect"))
    )
    (net (code "62") (name "unconnected-(U28-NC-Pad10)") (class "Default")
      (node (ref "U28") (pin "10") (pinfunction "NC_10") (pintype "unspecified+no_connect"))
    )
    (net (code "63") (name "unconnected-(U28-RI{slash}CLK-Pad2)") (class "Default")
      (node (ref "U28") (pin "2") (pinfunction "RI/CLK_2") (pintype "unspecified+no_connect"))
    )
    (net (code "64") (name "unconnected-(U28-SUSPEND-Pad12)") (class "Default")
      (node (ref "U28") (pin "12") (pinfunction "SUSPEND_12") (pintype "unspecified+no_connect"))
    )
    (net (code "65") (name "unconnected-(U28-SUSPENDb-Pad11)") (class "Default")
      (node (ref "U28") (pin "11") (pinfunction "SUSPENDb_11") (pintype "unspecified+no_connect"))
    )
    (net (code "66") (name "unconnected-(U29-IO2-Pad24)") (class "Default")
      (node (ref "U29") (pin "24") (pinfunction "IO2_24") (pintype "unspecified+no_connect"))
    )
    (net (code "67") (name "unconnected-(U29-IO4-Pad26)") (class "Default")
      (node (ref "U29") (pin "26") (pinfunction "IO4_26") (pintype "unspecified+no_connect"))
    )
    (net (code "68") (name "unconnected-(U29-IO12-Pad14)") (class "Default")
      (node (ref "U29") (pin "14") (pinfunction "IO12_14") (pintype "unspecified+no_connect"))
    )
    (net (code "69") (name "unconnected-(U29-IO13-Pad16)") (class "Default")
      (node (ref "U29") (pin "16") (pinfunction "IO13_16") (pintype "unspecified+no_connect"))
    )
    (net (code "70") (name "unconnected-(U29-IO14-Pad13)") (class "Default")
      (node (ref "U29") (pin "13") (pinfunction "IO14_13") (pintype "unspecified+no_connect"))
    )
    (net (code "71") (name "unconnected-(U29-IO15-Pad23)") (class "Default")
      (node (ref "U29") (pin "23") (pinfunction "IO15_23") (pintype "unspecified+no_connect"))
    )
    (net (code "72") (name "unconnected-(U29-IO25-Pad10)") (class "Default")
      (node (ref "U29") (pin "10") (pinfunction "IO25_10") (pintype "unspecified+no_connect"))
    )
    (net (code "73") (name "unconnected-(U29-IO26-Pad11)") (class "Default")
      (node (ref "U29") (pin "11") (pinfunction "IO26_11") (pintype "unspecified+no_connect"))
    )
    (net (code "74") (name "unconnected-(U29-IO27-Pad12)") (class "Default")
      (node (ref "U29") (pin "12") (pinfunction "IO27_12") (pintype "unspecified+no_connect"))
    )
    (net (code "75") (name "unconnected-(U29-IO32-Pad8)") (class "Default")
      (node (ref "U29") (pin "8") (pinfunction "IO32_8") (pintype "unspecified+no_connect"))
    )
    (net (code "76") (name "unconnected-(U29-IO33-Pad9)") (class "Default")
      (node (ref "U29") (pin "9") (pinfunction "IO33_9") (pintype "unspecified+no_connect"))
    )
    (net (code "77") (name "unconnected-(U29-IO34-Pad6)") (class "Default")
      (node (ref "U29") (pin "6") (pinfunction "IO34_6") (pintype "unspecified+no_connect"))
    )
    (net (code "78") (name "unconnected-(U29-NC-Pad32)") (class "Default")
      (node (ref "U29") (pin "32") (pinfunction "NC_32") (pintype "unspecified+no_connect"))
    )
    (net (code "79") (name "unconnected-(U29-SCK{slash}CLK-Pad20)") (class "Default")
      (node (ref "U29") (pin "20") (pinfunction "SCK/CLK_20") (pintype "unspecified+no_connect"))
    )
    (net (code "80") (name "unconnected-(U29-SCS{slash}CMD-Pad19)") (class "Default")
      (node (ref "U29") (pin "19") (pinfunction "SCS/CMD_19") (pintype "unspecified+no_connect"))
    )
    (net (code "81") (name "unconnected-(U29-SDI{slash}SD1-Pad22)") (class "Default")
      (node (ref "U29") (pin "22") (pinfunction "SDI/SD1_22") (pintype "unspecified+no_connect"))
    )
    (net (code "82") (name "unconnected-(U29-SDO{slash}SD0-Pad21)") (class "Default")
      (node (ref "U29") (pin "21") (pinfunction "SDO/SD0_21") (pintype "unspecified+no_connect"))
    )
    (net (code "83") (name "unconnected-(U29-SENSOR_VN-Pad5)") (class "Default")
      (node (ref "U29") (pin "5") (pinfunction "SENSOR_VN_5") (pintype "unspecified+no_connect"))
    )
    (net (code "84") (name "unconnected-(U29-SENSOR_VP-Pad4)") (class "Default")
      (node (ref "U29") (pin "4") (pinfunction "SENSOR_VP_4") (pintype "unspecified+no_connect"))
    )
    (net (code "85") (name "unconnected-(U29-SHD{slash}SD2-Pad17)") (class "Default")
      (node (ref "U29") (pin "17") (pinfunction "SHD/SD2_17") (pintype "unspecified+no_connect"))
    )
    (net (code "86") (name "unconnected-(U29-SWP{slash}SD3-Pad18)") (class "Default")
      (node (ref "U29") (pin "18") (pinfunction "SWP/SD3_18") (pintype "unspecified+no_connect"))
    )
    (net (code "87") (name "unconnected-(USB1-ID-Pad4)") (class "Default")
      (node (ref "USB1") (pin "4") (pinfunction "ID_4") (pintype "unspecified+no_connect"))
    )
  )
)
